# mcu.net
KiCad netlist of a schematic drawn in Altium Designer
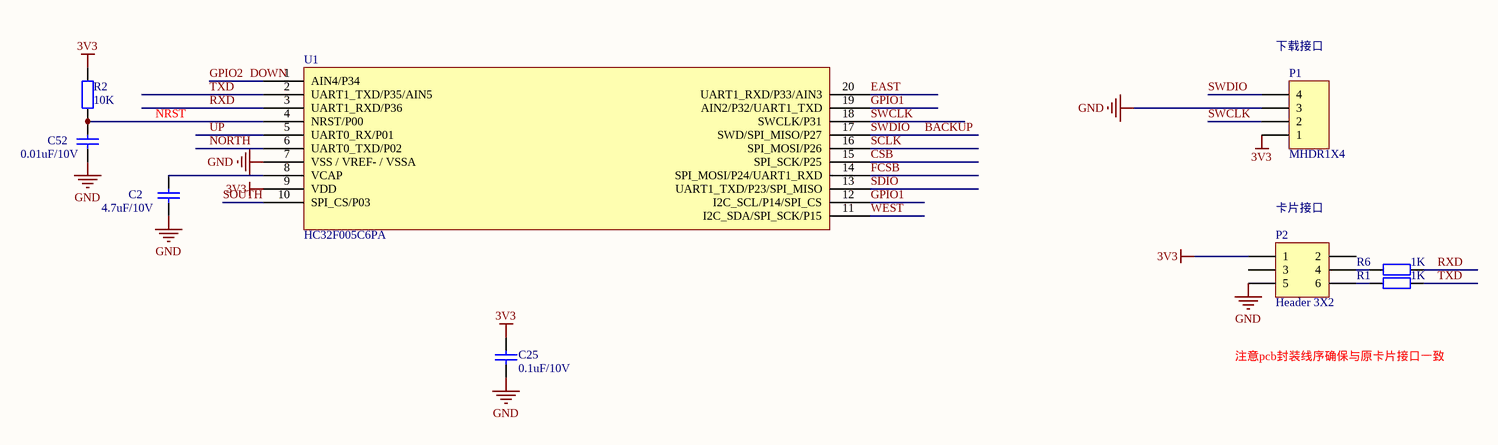
[diagram p0: mcu.SchDoc]

(export (version "E")
  (design (tool "Eeschema 10.0.6"))
  (components
    (comp (ref "C2")
      (value "4.7uF/10V")
      (footprint "0603C")
      (description "Capacitor")
      (fields (field (name "PUBLISHER") "Altium Limited"))
      (libsource (lib "Miscellaneous Devices") (part "Cap"))
    )
    (comp (ref "C25")
      (value "0.1uF/10V")
      (footprint "0603C")
      (description "Capacitor")
      (fields (field (name "PUBLISHER") "Altium Limited"))
      (libsource (lib "Miscellaneous Devices") (part "Cap"))
    )
    (comp (ref "C52")
      (value "0.01uF/10V")
      (footprint "0603C")
      (description "Capacitor")
      (fields (field (name "PUBLISHER") "Altium Limited"))
      (libsource (lib "Miscellaneous Devices") (part "Cap"))
    )
    (comp (ref "P1")
      (value "MHDR1X4")
      (footprint "SIP4")
      (description "Header, 4-Pin")
      (fields (field (name "PUBLISHER") "Altium Limited"))
      (libsource (lib "Miscellaneous Connectors") (part "MHDR1X4"))
    )
    (comp (ref "P2")
      (value "Header 3X2")
      (description "Header, 3-Pin, Dual row")
      (fields (field (name "PUBLISHER") "Altium Limited"))
      (libsource (lib "Miscellaneous Connectors") (part "Header 3X2"))
    )
    (comp (ref "R1")
      (value "1K")
      (footprint "0603R")
      (description "Resistor")
      (fields (field (name "PUBLISHER") "Altium Limited"))
      (libsource (lib "Miscellaneous Devices") (part "Res2"))
    )
    (comp (ref "R2")
      (value "10K")
      (footprint "0603R")
      (description "Resistor")
      (fields (field (name "PUBLISHER") "Altium Limited"))
      (libsource (lib "") (part "Res2_1"))
    )
    (comp (ref "R6")
      (value "1K")
      (footprint "0603R")
      (description "Resistor")
      (fields (field (name "PUBLISHER") "Altium Limited"))
      (libsource (lib "Miscellaneous Devices") (part "Res2"))
    )
    (comp (ref "U1") (value "HC32F005C6PA") (libsource (lib "Schlib_20110825") (part "HC32F005C6PA")))
  )
  (nets
    (net (code "1") (name "/BACKUP") (class "Default")
      (node (ref "P1") (pin "4") (pinfunction "4_4") (pintype "passive"))
      (node (ref "U1") (pin "17") (pinfunction "SWD/SPI_MISO/P27_17") (pintype "passive"))
    )
    (net (code "2") (name "/CSB") (class "Default")
      (node (ref "U1") (pin "15") (pinfunction "SPI_SCK/P25_15") (pintype "passive"))
    )
    (net (code "3") (name "/DOWN") (class "Default")
      (node (ref "U1") (pin "1") (pinfunction "AIN4/P34_1") (pintype "passive"))
    )
    (net (code "4") (name "/EAST") (class "Default")
      (node (ref "U1") (pin "20") (pinfunction "UART1_RXD/P33/AIN3_20") (pintype "passive"))
    )
    (net (code "5") (name "/FCSB") (class "Default")
      (node (ref "U1") (pin "14") (pinfunction "SPI_MOSI/P24/UART1_RXD_14") (pintype "passive"))
    )
    (net (code "6") (name "/GPIO1") (class "Default")
      (node (ref "U1") (pin "12") (pinfunction "I2C_SCL/P14/SPI_CS_12") (pintype "passive"))
      (node (ref "U1") (pin "19") (pinfunction "AIN2/P32/UART1_TXD_19") (pintype "passive"))
    )
    (net (code "7") (name "/NORTH") (class "Default")
      (node (ref "U1") (pin "6") (pinfunction "UART0_TXD/P02_6") (pintype "passive"))
    )
    (net (code "8") (name "/NRST") (class "Default")
      (node (ref "C52") (pin "1") (pinfunction "1_1") (pintype "passive"))
      (node (ref "R2") (pin "1") (pinfunction "1_1") (pintype "passive"))
      (node (ref "U1") (pin "4") (pinfunction "NRST/P00_4") (pintype "passive"))
    )
    (net (code "9") (name "/RXD") (class "Default")
      (node (ref "R6") (pin "1") (pinfunction "1_1") (pintype "passive"))
      (node (ref "U1") (pin "3") (pinfunction "UART1_RXD/P36_3") (pintype "passive"))
    )
    (net (code "10") (name "/SCLK") (class "Default")
      (node (ref "U1") (pin "16") (pinfunction "SPI_MOSI/P26_16") (pintype "passive"))
    )
    (net (code "11") (name "/SDIO") (class "Default")
      (node (ref "U1") (pin "13") (pinfunction "UART1_TXD/P23/SPI_MISO_13") (pintype "passive"))
    )
    (net (code "12") (name "/SOUTH") (class "Default")
      (node (ref "U1") (pin "10") (pinfunction "SPI_CS/P03_10") (pintype "passive"))
    )
    (net (code "13") (name "/SWCLK") (class "Default")
      (node (ref "P1") (pin "2") (pinfunction "2_2") (pintype "passive"))
      (node (ref "U1") (pin "18") (pinfunction "SWCLK/P31_18") (pintype "passive"))
    )
    (net (code "14") (name "/TXD") (class "Default")
      (node (ref "R1") (pin "1") (pinfunction "1_1") (pintype "passive"))
      (node (ref "U1") (pin "2") (pinfunction "UART1_TXD/P35/AIN5_2") (pintype "passive"))
    )
    (net (code "15") (name "/UP") (class "Default")
      (node (ref "U1") (pin "5") (pinfunction "UART0_RX/P01_5") (pintype "passive"))
    )
    (net (code "16") (name "/WEST") (class "Default")
      (node (ref "U1") (pin "11") (pinfunction "I2C_SDA/SPI_SCK/P15_11") (pintype "passive"))
    )
    (net (code "17") (name "3V3") (class "Default")
      (node (ref "C25") (pin "1") (pinfunction "1_1") (pintype "passive"))
      (node (ref "P1") (pin "1") (pinfunction "1_1") (pintype "passive"))
      (node (ref "P2") (pin "1") (pinfunction "1_1") (pintype "passive"))
      (node (ref "R2") (pin "2") (pinfunction "2_2") (pintype "passive"))
      (node (ref "U1") (pin "9") (pinfunction "VDD_9") (pintype "passive"))
    )
    (net (code "18") (name "GND") (class "Default")
      (node (ref "C2") (pin "2") (pinfunction "2_2") (pintype "passive"))
      (node (ref "C25") (pin "2") (pinfunction "2_2") (pintype "passive"))
      (node (ref "C52") (pin "2") (pinfunction "2_2") (pintype "passive"))
      (node (ref "P1") (pin "3") (pinfunction "3_3") (pintype "passive"))
      (node (ref "P2") (pin "5") (pinfunction "5_5") (pintype "passive"))
      (node (ref "U1") (pin "7") (pinfunction "VSS_/_VREF-_/_VSSA_7") (pintype "passive"))
    )
    (net (code "19") (name "Net-(P2-Pad4)") (class "Default")
      (node (ref "P2") (pin "4") (pinfunction "4_4") (pintype "passive"))
      (node (ref "R6") (pin "2") (pinfunction "2_2") (pintype "passive"))
    )
    (net (code "20") (name "Net-(P2-Pad6)") (class "Default")
      (node (ref "P2") (pin "6") (pinfunction "6_6") (pintype "passive"))
      (node (ref "R1") (pin "2") (pinfunction "2_2") (pintype "passive"))
    )
    (net (code "21") (name "Net-(U1-VCAP)") (class "Default")
      (node (ref "C2") (pin "1") (pinfunction "1_1") (pintype "passive"))
      (node (ref "U1") (pin "8") (pinfunction "VCAP_8") (pintype "passive"))
    )
    (net (code "22") (name "unconnected-(P2-Pad2)") (class "Default")
      (node (ref "P2") (pin "2") (pinfunction "2_2") (pintype "passive"))
    )
    (net (code "23") (name "unconnected-(P2-Pad3)") (class "Default")
      (node (ref "P2") (pin "3") (pinfunction "3_3") (pintype "passive"))
    )
  )
)
